# ADT7410_termometr2_minibord.net
KiCad netlist of a schematic drawn in EAGLE
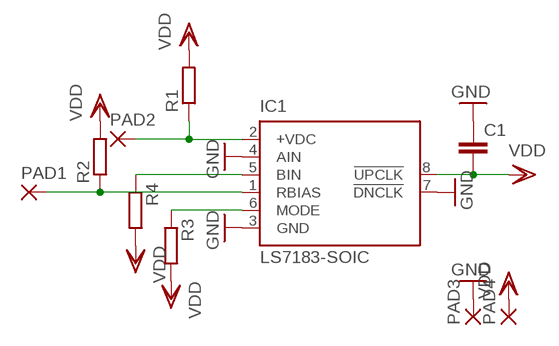
[diagram p0: schematic, sheet 1]

(export (version "E")
  (design (tool "Eeschema 10.0.6"))
  (components
    (comp (ref "C1")
      (value "C-EUC0805")
      (footprint "eagle-import:C0805")
      (libsource (lib "eagle-import") (part "C-EUC0805"))
    )
    (comp (ref "IC1")
      (value "LS7183-SOIC")
      (footprint "eagle-import:SOIC08")
      (libsource (lib "eagle-import") (part "LS7183-SOIC"))
    )
    (comp (ref "PAD1")
      (value "1,6/0,8")
      (footprint "eagle-import:1,6_0,8")
      (libsource (lib "eagle-import") (part "1,6/0,8"))
    )
    (comp (ref "PAD2")
      (value "1,6/0,8")
      (footprint "eagle-import:1,6_0,8")
      (libsource (lib "eagle-import") (part "1,6/0,8"))
    )
    (comp (ref "PAD3")
      (value "1,6/0,8")
      (footprint "eagle-import:1,6_0,8")
      (libsource (lib "eagle-import") (part "1,6/0,8"))
    )
    (comp (ref "PAD4")
      (value "1,6/0,8")
      (footprint "eagle-import:1,6_0,8")
      (libsource (lib "eagle-import") (part "1,6/0,8"))
    )
    (comp (ref "R1")
      (value "R-EU_M0805")
      (footprint "eagle-import:M0805")
      (libsource (lib "eagle-import") (part "R-EU_M0805"))
    )
    (comp (ref "R2")
      (value "R-EU_M0805")
      (footprint "eagle-import:M0805")
      (libsource (lib "eagle-import") (part "R-EU_M0805"))
    )
    (comp (ref "R3")
      (value "R-EU_M0805")
      (footprint "eagle-import:M0805")
      (libsource (lib "eagle-import") (part "R-EU_M0805"))
    )
    (comp (ref "R4")
      (value "R-EU_M0805")
      (footprint "eagle-import:M0805")
      (libsource (lib "eagle-import") (part "R-EU_M0805"))
    )
  )
  (nets
    (net (code "1") (name "GND") (class "Default")
      (node (ref "C1") (pin "1") (pinfunction "1_1") (pintype "passive"))
      (node (ref "IC1") (pin "3") (pinfunction "GND_3") (pintype "power_in"))
      (node (ref "IC1") (pin "4") (pinfunction "AIN_4") (pintype "input"))
      (node (ref "IC1") (pin "7") (pinfunction "~{DNCLK}_7") (pintype "input"))
      (node (ref "PAD3") (pin "1") (pinfunction "P_1") (pintype "passive"))
    )
    (net (code "2") (name "Net-(IC1-+VDC)") (class "Default")
      (node (ref "IC1") (pin "2") (pinfunction "+VDC_2") (pintype "input"))
      (node (ref "PAD2") (pin "1") (pinfunction "P_1") (pintype "passive"))
      (node (ref "R1") (pin "1") (pinfunction "1_1") (pintype "passive"))
    )
    (net (code "3") (name "Net-(IC1-BIN)") (class "Default")
      (node (ref "IC1") (pin "5") (pinfunction "BIN_5") (pintype "input"))
      (node (ref "R4") (pin "1") (pinfunction "1_1") (pintype "passive"))
    )
    (net (code "4") (name "Net-(IC1-MODE)") (class "Default")
      (node (ref "IC1") (pin "6") (pinfunction "MODE_6") (pintype "input"))
      (node (ref "R3") (pin "1") (pinfunction "1_1") (pintype "passive"))
    )
    (net (code "5") (name "Net-(IC1-RBIAS)") (class "Default")
      (node (ref "IC1") (pin "1") (pinfunction "RBIAS_1") (pintype "input"))
      (node (ref "PAD1") (pin "1") (pinfunction "P_1") (pintype "passive"))
      (node (ref "R2") (pin "1") (pinfunction "1_1") (pintype "passive"))
    )
    (net (code "6") (name "VDD") (class "Default")
      (node (ref "C1") (pin "2") (pinfunction "2_2") (pintype "passive"))
      (node (ref "IC1") (pin "8") (pinfunction "~{UPCLK}_8") (pintype "input"))
      (node (ref "PAD4") (pin "1") (pinfunction "P_1") (pintype "passive"))
      (node (ref "R1") (pin "2") (pinfunction "2_2") (pintype "passive"))
      (node (ref "R2") (pin "2") (pinfunction "2_2") (pintype "passive"))
      (node (ref "R3") (pin "2") (pinfunction "2_2") (pintype "passive"))
      (node (ref "R4") (pin "2") (pinfunction "2_2") (pintype "passive"))
    )
  )
)
